# Converters.net
KiCad netlist of a schematic drawn in Altium Designer
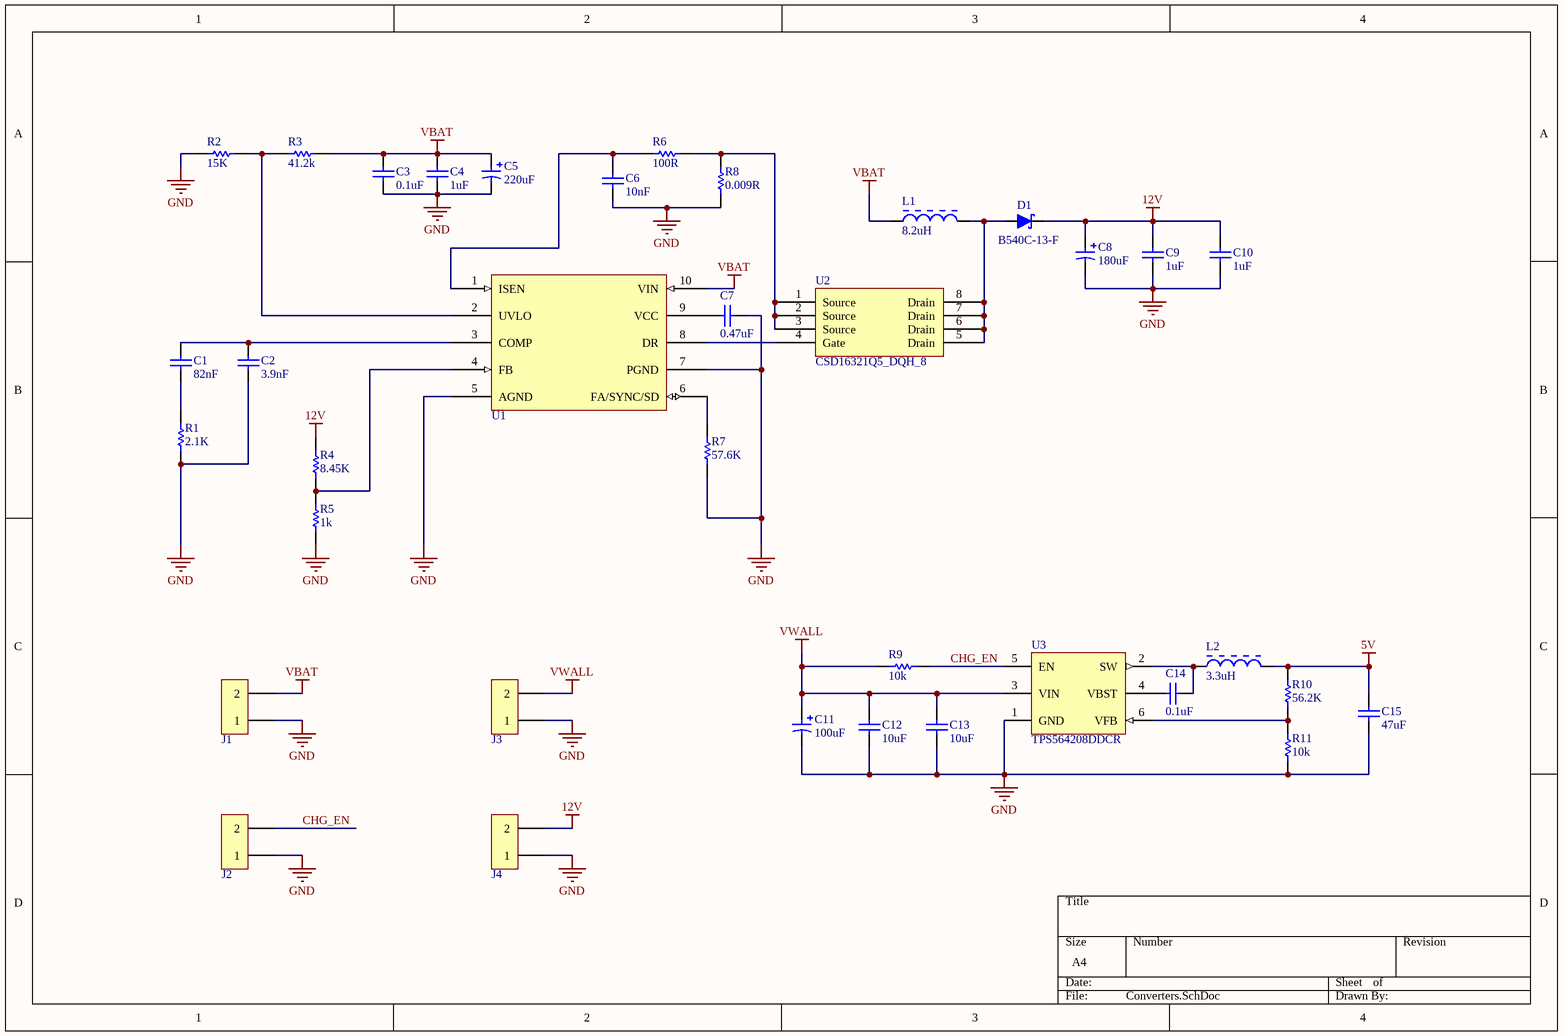
[diagram p0: Converters.SchDoc]

(export (version "E")
  (design (tool "Eeschema 10.0.6"))
  (components
    (comp (ref "C1")
      (value "82nF")
      (footprint "CAPC1608X09N")
      (fields
        (field (name "DIGIKEY PART NUMBER") "490-6434-1-ND")
        (field (name "MANUFACTURER") "Murata")
        (field (name "VOLTAGE") "25V")
      )
      (libsource (lib "Speaker Library") (part "CAP CER 82nF 0603"))
    )
    (comp (ref "C2")
      (value "3.9nF")
      (footprint "CAPC1608X09N")
      (fields
        (field (name "DIGIKEY PART NUMBER") "490-11525-1-ND")
        (field (name "MANUFACTURER") "Murata")
        (field (name "VOLTAGE") "25V")
      )
      (libsource (lib "Speaker Library") (part "CAP CER 3.9nF 0603"))
    )
    (comp (ref "C3")
      (value "0.1uF")
      (footprint "CAPC1608X09N")
      (fields
        (field (name "DIGIKEY PART NUMBER") "490-1519-1-ND")
        (field (name "VOLTAGE") "50V")
        (field (name "TOLERANCE") "10%")
      )
      (libsource (lib "Speaker Library") (part "CAP CER 0.1uF 0603"))
    )
    (comp (ref "C4")
      (value "1uF")
      (footprint "CAPC1608X09N")
      (fields (field (name "DIGIKEY PART NUMBER") "490-10487-1-ND") (field (name "VOLTAGE") "35V"))
      (libsource (lib "Speaker Library") (part "CAP CER 1uF 0603"))
    )
    (comp (ref "C5")
      (value "220uF")
      (footprint "UUD1V221MNL1GS")
      (fields
        (field (name "DIGIKEY PART NUMBER") "493-2292-1-ND")
        (field (name "MANUFACTURER") "Nichicon")
        (field (name "VOLTAGE") "35V")
      )
      (libsource (lib "Speaker Library") (part "CAP ALUM 220uF SMD"))
    )
    (comp (ref "C6")
      (value "10nF")
      (footprint "CAPC1608X09N")
      (description "Bypass caps")
      (fields (field (name "DIGIKEY PART NUMBER") "490-9666-1-ND") (field (name "MANUFACTURER") "Murata"))
      (libsource (lib "Speaker Library") (part "CAP CER 10nF 0603"))
    )
    (comp (ref "C7")
      (value "0.47uF")
      (footprint "CAPC1608X09N")
      (fields (field (name "DIGIKEY PART NUMBER") "490-3291-1-ND") (field (name "VOLTAGE") "25V"))
      (libsource (lib "Speaker Library") (part "CAP CER 0.47uF 0603"))
    )
    (comp (ref "C8")
      (value "180uF")
      (footprint "PCAP_SVP_E12-M")
      (fields
        (field (name "DIGIKEY PART NUMBER") "P16510CT-ND")
        (field (name "MANUFACTURER") "Panasonic")
        (field (name "VOLTAGE") "25V")
      )
      (libsource (lib "Speaker Library") (part "CAP ALUM 180uF SMD"))
    )
    (comp (ref "C9")
      (value "1uF")
      (footprint "CAPC1608X09N")
      (fields (field (name "DIGIKEY PART NUMBER") "490-10487-1-ND") (field (name "VOLTAGE") "35V"))
      (libsource (lib "Speaker Library") (part "CAP CER 1uF 0603"))
    )
    (comp (ref "C10")
      (value "1uF")
      (footprint "CAPC1608X09N")
      (fields (field (name "DIGIKEY PART NUMBER") "490-10487-1-ND") (field (name "VOLTAGE") "35V"))
      (libsource (lib "Speaker Library") (part "CAP CER 1uF 0603"))
    )
    (comp (ref "C11")
      (value "100uF")
      (footprint "PCAP_8x10-ELEC00")
      (fields
        (field (name "DIGIKEY PART NUMBER") "493-2226-1-ND")
        (field (name "MANUFACTURER") "Nichicon")
        (field (name "VOLTAGE") "50V")
      )
      (libsource (lib "Speaker Library") (part "CAP ALUM 100uF SMD"))
    )
    (comp (ref "C12")
      (value "10uF")
      (footprint "CAPC3216X18N")
      (description "3V3 filter cap")
      (fields (field (name "DIGIKEY PART NUMBER") "490-6518-1-ND") (field (name "VOLTAGE") "25V"))
      (libsource (lib "Speaker Library") (part "CAP CER 10uF 1206"))
    )
    (comp (ref "C13")
      (value "10uF")
      (footprint "CAPC3216X18N")
      (description "3V3 filter cap")
      (fields (field (name "DIGIKEY PART NUMBER") "490-6518-1-ND") (field (name "VOLTAGE") "25V"))
      (libsource (lib "Speaker Library") (part "CAP CER 10uF 1206"))
    )
    (comp (ref "C14")
      (value "0.1uF")
      (footprint "CAPC1608X09N")
      (fields
        (field (name "DIGIKEY PART NUMBER") "490-1519-1-ND")
        (field (name "VOLTAGE") "50V")
        (field (name "TOLERANCE") "10%")
      )
      (libsource (lib "Speaker Library") (part "CAP CER 0.1uF 0603"))
    )
    (comp (ref "C15")
      (value "47uF")
      (footprint "CAPC3225X25M")
      (fields
        (field (name "DIGIKEY PART NUMBER") "490-6538-1-ND")
        (field (name "VOLTAGE") "16V")
        (field (name "TOLERANCE") "10%")
      )
      (libsource (lib "Speaker Library") (part "CAP CER 47uF X5R 1210"))
    )
    (comp (ref "D1")
      (value "B540C-13-F")
      (footprint "DIOM6959X25N")
      (description "Diode Schottky 40V 5A SMT")
      (fields (field (name "VOLTAGE") "40V") (field (name "DIGIKEY PART NUMBER") "B540C-FDICT-ND"))
      (libsource (lib "Speaker Library") (part "B540C-13-F"))
    )
    (comp (ref "J1")
      (value "2POS THRU HOLE 2.54MM")
      (footprint "2POS Through Hole 2.54MM")
      (libsource (lib "Speaker Library") (part "2POS THRU HOLE 2.54MM"))
    )
    (comp (ref "J2")
      (value "2POS THRU HOLE 2.54MM")
      (footprint "2POS Through Hole 2.54MM")
      (libsource (lib "Speaker Library") (part "2POS THRU HOLE 2.54MM"))
    )
    (comp (ref "J3")
      (value "2POS THRU HOLE 2.54MM")
      (footprint "2POS Through Hole 2.54MM")
      (libsource (lib "Speaker Library") (part "2POS THRU HOLE 2.54MM"))
    )
    (comp (ref "J4")
      (value "2POS THRU HOLE 2.54MM")
      (footprint "2POS Through Hole 2.54MM")
      (libsource (lib "Speaker Library") (part "2POS THRU HOLE 2.54MM"))
    )
    (comp (ref "L1")
      (value "8.2uH")
      (footprint "SRP1270")
      (fields (field (name "DIGIKEY PART NUMBER") "SRP1270-8R2MCT-ND"))
      (libsource (lib "Speaker Library") (part "IND 8.2uH 11A SMD NONSTANDARD"))
    )
    (comp (ref "L2")
      (value "3.3uH")
      (footprint "IND_BOURNS_SRP00")
      (fields (field (name "DIGIKEY PART NUMBER") "SRP7030-3R3FMCT-ND"))
      (libsource (lib "Speaker Library") (part "IND 3.3µH 7A SMD"))
    )
    (comp (ref "R1")
      (value "2.1K")
      (footprint "RESC1608X06N")
      (fields
        (field (name "TOLERANCE") "1%")
        (field (name "POWER") "0.1W")
        (field (name "MANUFACTURER") "Yageo")
      )
      (libsource (lib "Speaker Library") (part "RES 2.1K 0603"))
    )
    (comp (ref "R2")
      (value "15K")
      (footprint "RESC1608X06N")
      (fields (field (name "TOLERANCE") "1%") (field (name "DIGIKEY PART NUMBER") "311-15.0KHRCT-ND"))
      (libsource (lib "Speaker Library") (part "RES 15K 0603"))
    )
    (comp (ref "R3")
      (value "41.2k")
      (footprint "RESC1608X06N")
      (fields
        (field (name "TOLERANCE") "1%")
        (field (name "POWER") "0.1W")
        (field (name "MANUFACTURER") "Vishay Dale")
      )
      (libsource (lib "Speaker Library") (part "RES 41.2K 0603"))
    )
    (comp (ref "R4")
      (value "8.45K")
      (footprint "RESC1608X06N")
      (fields
        (field (name "TOLERANCE") "1%")
        (field (name "POWER") "0.1W")
        (field (name "MANUFACTURER") "Vishay Dale")
      )
      (libsource (lib "Speaker Library") (part "RES 8.45K 0603"))
    )
    (comp (ref "R5")
      (value "1k")
      (footprint "RESC1608X06N")
      (fields
        (field (name "TOLERANCE") "1%")
        (field (name "POWER") "0.25W")
        (field (name "MANUFACTURER") "Panasonic")
      )
      (libsource (lib "Speaker Library") (part "RES 1K 0603"))
    )
    (comp (ref "R6")
      (value "100R")
      (footprint "RESC1608X06N")
      (fields
        (field (name "TOLERANCE") "1%")
        (field (name "POWER") "0.25W")
        (field (name "DIGIKEY PART NUMBER") "541-100SACT-ND")
      )
      (libsource (lib "Speaker Library") (part "RES 100R 0603"))
    )
    (comp (ref "R7")
      (value "57.6K")
      (footprint "RESC1608X06N")
      (fields
        (field (name "TOLERANCE") "1%")
        (field (name "POWER") "0.1W")
        (field (name "MANUFACTURER") "Yageo")
      )
      (libsource (lib "Speaker Library") (part "RES 57.6K 0603"))
    )
    (comp (ref "R8")
      (value "0.009R")
      (footprint "RESC3216X07N")
      (fields
        (field (name "TOLERANCE") "1%")
        (field (name "POWER") "1W")
        (field (name "MANUFACTURER") "Rohm Semiconductor")
      )
      (libsource (lib "Speaker Library") (part "RES 0.009R 1206"))
    )
    (comp (ref "R9")
      (value "10k")
      (footprint "RESC1608X06N")
      (fields
        (field (name "TOLERANCE") "1%")
        (field (name "POWER") "0.1W")
        (field (name "MANUFACTURER") "Yageo")
      )
      (libsource (lib "Speaker Library") (part "RES 10K 0603"))
    )
    (comp (ref "R10")
      (value "56.2K")
      (footprint "RESC1608X06N")
      (fields
        (field (name "TOLERANCE") "1%")
        (field (name "POWER") "0.1W")
        (field (name "MANUFACTURER") "Yageo")
      )
      (libsource (lib "Speaker Library") (part "RES 56.2K 0603"))
    )
    (comp (ref "R11")
      (value "10k")
      (footprint "RESC1608X06N")
      (fields
        (field (name "TOLERANCE") "1%")
        (field (name "POWER") "0.1W")
        (field (name "MANUFACTURER") "Yageo")
      )
      (libsource (lib "Speaker Library") (part "RES 10K 0603"))
    )
    (comp (ref "U1")
      (value "LM3481")
      (footprint "VSSOP10")
      (description "IC REG CTRLR MULT TOP 10MSOP")
      (fields (field (name "DIGIKEY PART NUMBER") "LM3481MM/NOPBCT-ND"))
      (libsource (lib "Speaker Library") (part "LM3481"))
    )
    (comp (ref "U2")
      (value "CSD16321Q5_DQH_8")
      (footprint "DQH8")
      (fields
        (field (name "MANUFACTURER") "Texas Instruments")
        (field (name "GENERIC_PART_NUMBER") "CSD16321Q5")
        (field (name "DIGIKEY PART NUMBER") "296-25643-1-ND")
      )
      (libsource (lib "Speaker Library") (part "CSD16321Q5_DQH_8"))
    )
    (comp (ref "U3")
      (value "TPS564208DDCR")
      (footprint "SOT95P280X110-6N (DDC)")
      (description "Regulator, Buck, 4.5V-17V Input, SOT-23")
      (fields
        (field (name "MANUFACTURER") "Texas Instruments")
        (field (name "DIGIKEY PART NUMBER") "296-44123-1-ND")
      )
      (libsource (lib "Speaker Library") (part "TPS564208DDCR"))
    )
  )
  (nets
    (net (code "1") (name "/CHG_EN") (class "Default")
      (node (ref "J2") (pin "2") (pinfunction "2_2") (pintype "passive"))
      (node (ref "R9") (pin "2") (pinfunction "2_2") (pintype "passive"))
      (node (ref "U3") (pin "5") (pinfunction "EN_5") (pintype "passive"))
    )
    (net (code "2") (name "5V") (class "Default")
      (node (ref "C15") (pin "2") (pinfunction "2_2") (pintype "passive"))
      (node (ref "L2") (pin "2") (pinfunction "2_2") (pintype "passive"))
      (node (ref "R10") (pin "2") (pinfunction "2_2") (pintype "passive"))
    )
    (net (code "3") (name "12V") (class "Default")
      (node (ref "C10") (pin "2") (pinfunction "2_2") (pintype "passive"))
      (node (ref "C8") (pin "1") (pinfunction "1_1") (pintype "passive"))
      (node (ref "C9") (pin "2") (pinfunction "2_2") (pintype "passive"))
      (node (ref "D1") (pin "2") (pinfunction "2_2") (pintype "passive"))
      (node (ref "J4") (pin "2") (pinfunction "2_2") (pintype "passive"))
      (node (ref "R4") (pin "1") (pinfunction "1_1") (pintype "passive"))
    )
    (net (code "4") (name "GND") (class "Default")
      (node (ref "C10") (pin "1") (pinfunction "1_1") (pintype "passive"))
      (node (ref "C11") (pin "2") (pinfunction "2_2") (pintype "passive"))
      (node (ref "C12") (pin "1") (pinfunction "1_1") (pintype "passive"))
      (node (ref "C13") (pin "1") (pinfunction "1_1") (pintype "passive"))
      (node (ref "C15") (pin "1") (pinfunction "1_1") (pintype "passive"))
      (node (ref "C2") (pin "1") (pinfunction "1_1") (pintype "passive"))
      (node (ref "C3") (pin "1") (pinfunction "1_1") (pintype "passive"))
      (node (ref "C4") (pin "1") (pinfunction "1_1") (pintype "passive"))
      (node (ref "C5") (pin "2") (pinfunction "2_2") (pintype "passive"))
      (node (ref "C6") (pin "1") (pinfunction "1_1") (pintype "passive"))
      (node (ref "C7") (pin "2") (pinfunction "2_2") (pintype "passive"))
      (node (ref "C8") (pin "2") (pinfunction "2_2") (pintype "passive"))
      (node (ref "C9") (pin "1") (pinfunction "1_1") (pintype "passive"))
      (node (ref "J1") (pin "1") (pinfunction "1_1") (pintype "passive"))
      (node (ref "J2") (pin "1") (pinfunction "1_1") (pintype "passive"))
      (node (ref "J3") (pin "1") (pinfunction "1_1") (pintype "passive"))
      (node (ref "J4") (pin "1") (pinfunction "1_1") (pintype "passive"))
      (node (ref "R1") (pin "1") (pinfunction "1_1") (pintype "passive"))
      (node (ref "R11") (pin "1") (pinfunction "1_1") (pintype "passive"))
      (node (ref "R2") (pin "1") (pinfunction "1_1") (pintype "passive"))
      (node (ref "R5") (pin "1") (pinfunction "1_1") (pintype "passive"))
      (node (ref "R7") (pin "1") (pinfunction "1_1") (pintype "passive"))
      (node (ref "R8") (pin "1") (pinfunction "1_1") (pintype "passive"))
      (node (ref "U1") (pin "5") (pinfunction "AGND_5") (pintype "power_in"))
      (node (ref "U1") (pin "7") (pinfunction "PGND_7") (pintype "power_in"))
      (node (ref "U3") (pin "1") (pinfunction "GND_1") (pintype "power_in"))
    )
    (net (code "5") (name "Net-(C1-Pad1)") (class "Default")
      (node (ref "C1") (pin "1") (pinfunction "1_1") (pintype "passive"))
      (node (ref "R1") (pin "2") (pinfunction "2_2") (pintype "passive"))
    )
    (net (code "6") (name "Net-(D1-Pad1)") (class "Default")
      (node (ref "D1") (pin "1") (pinfunction "1_1") (pintype "passive"))
      (node (ref "L1") (pin "2") (pinfunction "2_2") (pintype "passive"))
      (node (ref "U2") (pin "5") (pinfunction "Drain_5") (pintype "passive"))
      (node (ref "U2") (pin "6") (pinfunction "Drain_6") (pintype "passive"))
      (node (ref "U2") (pin "7") (pinfunction "Drain_7") (pintype "passive"))
      (node (ref "U2") (pin "8") (pinfunction "Drain_8") (pintype "passive"))
    )
    (net (code "7") (name "Net-(R6-Pad2)") (class "Default")
      (node (ref "R6") (pin "2") (pinfunction "2_2") (pintype "passive"))
      (node (ref "R8") (pin "2") (pinfunction "2_2") (pintype "passive"))
      (node (ref "U2") (pin "1") (pinfunction "Source_1") (pintype "passive"))
      (node (ref "U2") (pin "2") (pinfunction "Source_2") (pintype "passive"))
      (node (ref "U2") (pin "3") (pinfunction "Source_3") (pintype "passive"))
    )
    (net (code "8") (name "Net-(U1-COMP)") (class "Default")
      (node (ref "C1") (pin "2") (pinfunction "2_2") (pintype "passive"))
      (node (ref "C2") (pin "2") (pinfunction "2_2") (pintype "passive"))
      (node (ref "U1") (pin "3") (pinfunction "COMP_3") (pintype "passive"))
    )
    (net (code "9") (name "Net-(U1-DR)") (class "Default")
      (node (ref "U1") (pin "8") (pinfunction "DR_8") (pintype "passive"))
      (node (ref "U2") (pin "4") (pinfunction "Gate_4") (pintype "passive"))
    )
    (net (code "10") (name "Net-(U1-FA{slash}SYNC{slash}SD)") (class "Default")
      (node (ref "R7") (pin "2") (pinfunction "2_2") (pintype "passive"))
      (node (ref "U1") (pin "6") (pinfunction "FA/SYNC/SD_6") (pintype "bidirectional"))
    )
    (net (code "11") (name "Net-(U1-FB)") (class "Default")
      (node (ref "R4") (pin "2") (pinfunction "2_2") (pintype "passive"))
      (node (ref "R5") (pin "2") (pinfunction "2_2") (pintype "passive"))
      (node (ref "U1") (pin "4") (pinfunction "FB_4") (pintype "input"))
    )
    (net (code "12") (name "Net-(U1-ISEN)") (class "Default")
      (node (ref "C6") (pin "2") (pinfunction "2_2") (pintype "passive"))
      (node (ref "R6") (pin "1") (pinfunction "1_1") (pintype "passive"))
      (node (ref "U1") (pin "1") (pinfunction "ISEN_1") (pintype "input"))
    )
    (net (code "13") (name "Net-(U1-UVLO)") (class "Default")
      (node (ref "R2") (pin "2") (pinfunction "2_2") (pintype "passive"))
      (node (ref "R3") (pin "1") (pinfunction "1_1") (pintype "passive"))
      (node (ref "U1") (pin "2") (pinfunction "UVLO_2") (pintype "passive"))
    )
    (net (code "14") (name "Net-(U1-VCC)") (class "Default")
      (node (ref "C7") (pin "1") (pinfunction "1_1") (pintype "passive"))
      (node (ref "U1") (pin "9") (pinfunction "VCC_9") (pintype "power_in"))
    )
    (net (code "15") (name "Net-(U3-SW)") (class "Default")
      (node (ref "C14") (pin "2") (pinfunction "2_2") (pintype "passive"))
      (node (ref "L2") (pin "1") (pinfunction "1_1") (pintype "passive"))
      (node (ref "U3") (pin "2") (pinfunction "SW_2") (pintype "output"))
    )
    (net (code "16") (name "Net-(U3-VBST)") (class "Default")
      (node (ref "C14") (pin "1") (pinfunction "1_1") (pintype "passive"))
      (node (ref "U3") (pin "4") (pinfunction "VBST_4") (pintype "passive"))
    )
    (net (code "17") (name "Net-(U3-VFB)") (class "Default")
      (node (ref "R10") (pin "1") (pinfunction "1_1") (pintype "passive"))
      (node (ref "R11") (pin "2") (pinfunction "2_2") (pintype "passive"))
      (node (ref "U3") (pin "6") (pinfunction "VFB_6") (pintype "input"))
    )
    (net (code "18") (name "VBAT") (class "Default")
      (node (ref "C3") (pin "2") (pinfunction "2_2") (pintype "passive"))
      (node (ref "C4") (pin "2") (pinfunction "2_2") (pintype "passive"))
      (node (ref "C5") (pin "1") (pinfunction "1_1") (pintype "passive"))
      (node (ref "J1") (pin "2") (pinfunction "2_2") (pintype "passive"))
      (node (ref "L1") (pin "1") (pinfunction "1_1") (pintype "passive"))
      (node (ref "R3") (pin "2") (pinfunction "2_2") (pintype "passive"))
      (node (ref "U1") (pin "10") (pinfunction "VIN_10") (pintype "input"))
    )
    (net (code "19") (name "VWALL") (class "Default")
      (node (ref "C11") (pin "1") (pinfunction "1_1") (pintype "passive"))
      (node (ref "C12") (pin "2") (pinfunction "2_2") (pintype "passive"))
      (node (ref "C13") (pin "2") (pinfunction "2_2") (pintype "passive"))
      (node (ref "J3") (pin "2") (pinfunction "2_2") (pintype "passive"))
      (node (ref "R9") (pin "1") (pinfunction "1_1") (pintype "passive"))
      (node (ref "U3") (pin "3") (pinfunction "VIN_3") (pintype "power_in"))
    )
  )
)
